# 2.net
KiCad netlist of a schematic drawn in EasyEDA
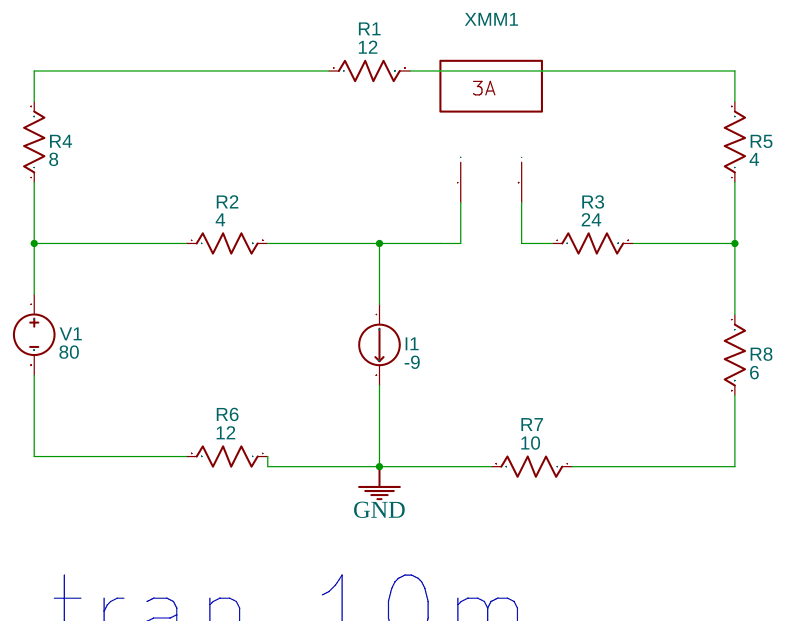
[diagram p0: schematic sheet]

(export (version "E")
  (design (tool "Eeschema 10.0.6"))
  (components
    (comp (ref "I1") (value "-9") (libsource (lib "") (part "IDC")))
    (comp (ref "R1") (value "12") (libsource (lib "") (part "Resistor_US_1")))
    (comp (ref "R2") (value "4") (libsource (lib "") (part "Resistor_US_1")))
    (comp (ref "R3") (value "24") (libsource (lib "") (part "Resistor_US_1")))
    (comp (ref "R4") (value "8") (libsource (lib "") (part "Resistor_US")))
    (comp (ref "R5") (value "4") (libsource (lib "") (part "Resistor_US")))
    (comp (ref "R6") (value "12") (libsource (lib "") (part "Resistor_US_3")))
    (comp (ref "R7") (value "10") (libsource (lib "") (part "Resistor_US_3")))
    (comp (ref "R8") (value "6") (libsource (lib "") (part "Resistor_US_2")))
    (comp (ref "V1") (value "80") (libsource (lib "") (part "VDC")))
    (comp (ref "XMM1") (value "Multimeter") (libsource (lib "") (part "MULTIMETER")))
  )
  (nets
    (net (code "1") (name "GND") (class "Default")
      (node (ref "I1") (pin "2") (pinfunction "2_2") (pintype "unspecified"))
      (node (ref "R6") (pin "1") (pinfunction "1_1") (pintype "unspecified"))
      (node (ref "R7") (pin "2") (pinfunction "2_2") (pintype "unspecified"))
    )
    (net (code "2") (name "Net-(R1-Pad1)") (class "Default")
      (node (ref "R1") (pin "1") (pinfunction "1_1") (pintype "unspecified"))
      (node (ref "R4") (pin "2") (pinfunction "2_2") (pintype "unspecified"))
    )
    (net (code "3") (name "Net-(R1-Pad2)") (class "Default")
      (node (ref "R1") (pin "2") (pinfunction "2_2") (pintype "unspecified"))
      (node (ref "R5") (pin "2") (pinfunction "2_2") (pintype "unspecified"))
    )
    (net (code "4") (name "Net-(R2-Pad1)") (class "Default")
      (node (ref "R2") (pin "1") (pinfunction "1_1") (pintype "unspecified"))
      (node (ref "R4") (pin "1") (pinfunction "1_1") (pintype "unspecified"))
      (node (ref "V1") (pin "1") (pinfunction "1_1") (pintype "unspecified"))
    )
    (net (code "5") (name "Net-(R3-Pad2)") (class "Default")
      (node (ref "R3") (pin "2") (pinfunction "2_2") (pintype "unspecified"))
      (node (ref "R5") (pin "1") (pinfunction "1_1") (pintype "unspecified"))
      (node (ref "R8") (pin "1") (pinfunction "1_1") (pintype "unspecified"))
    )
    (net (code "6") (name "Net-(R6-Pad2)") (class "Default")
      (node (ref "R6") (pin "2") (pinfunction "2_2") (pintype "unspecified"))
      (node (ref "V1") (pin "2") (pinfunction "2_2") (pintype "unspecified"))
    )
    (net (code "7") (name "Net-(R7-Pad1)") (class "Default")
      (node (ref "R7") (pin "1") (pinfunction "1_1") (pintype "unspecified"))
      (node (ref "R8") (pin "2") (pinfunction "2_2") (pintype "unspecified"))
    )
    (net (code "8") (name "Net-(XMM1-+)") (class "Default")
      (node (ref "I1") (pin "1") (pinfunction "1_1") (pintype "unspecified"))
      (node (ref "R2") (pin "2") (pinfunction "2_2") (pintype "unspecified"))
      (node (ref "XMM1") (pin "1") (pinfunction "+_1") (pintype "unspecified"))
    )
    (net (code "9") (name "Net-(XMM1-I)") (class "Default")
      (node (ref "R3") (pin "1") (pinfunction "1_1") (pintype "unspecified"))
      (node (ref "XMM1") (pin "2") (pinfunction "I_2") (pintype "unspecified"))
    )
  )
)
